# CD.net
KiCad netlist of a schematic drawn in EAGLE
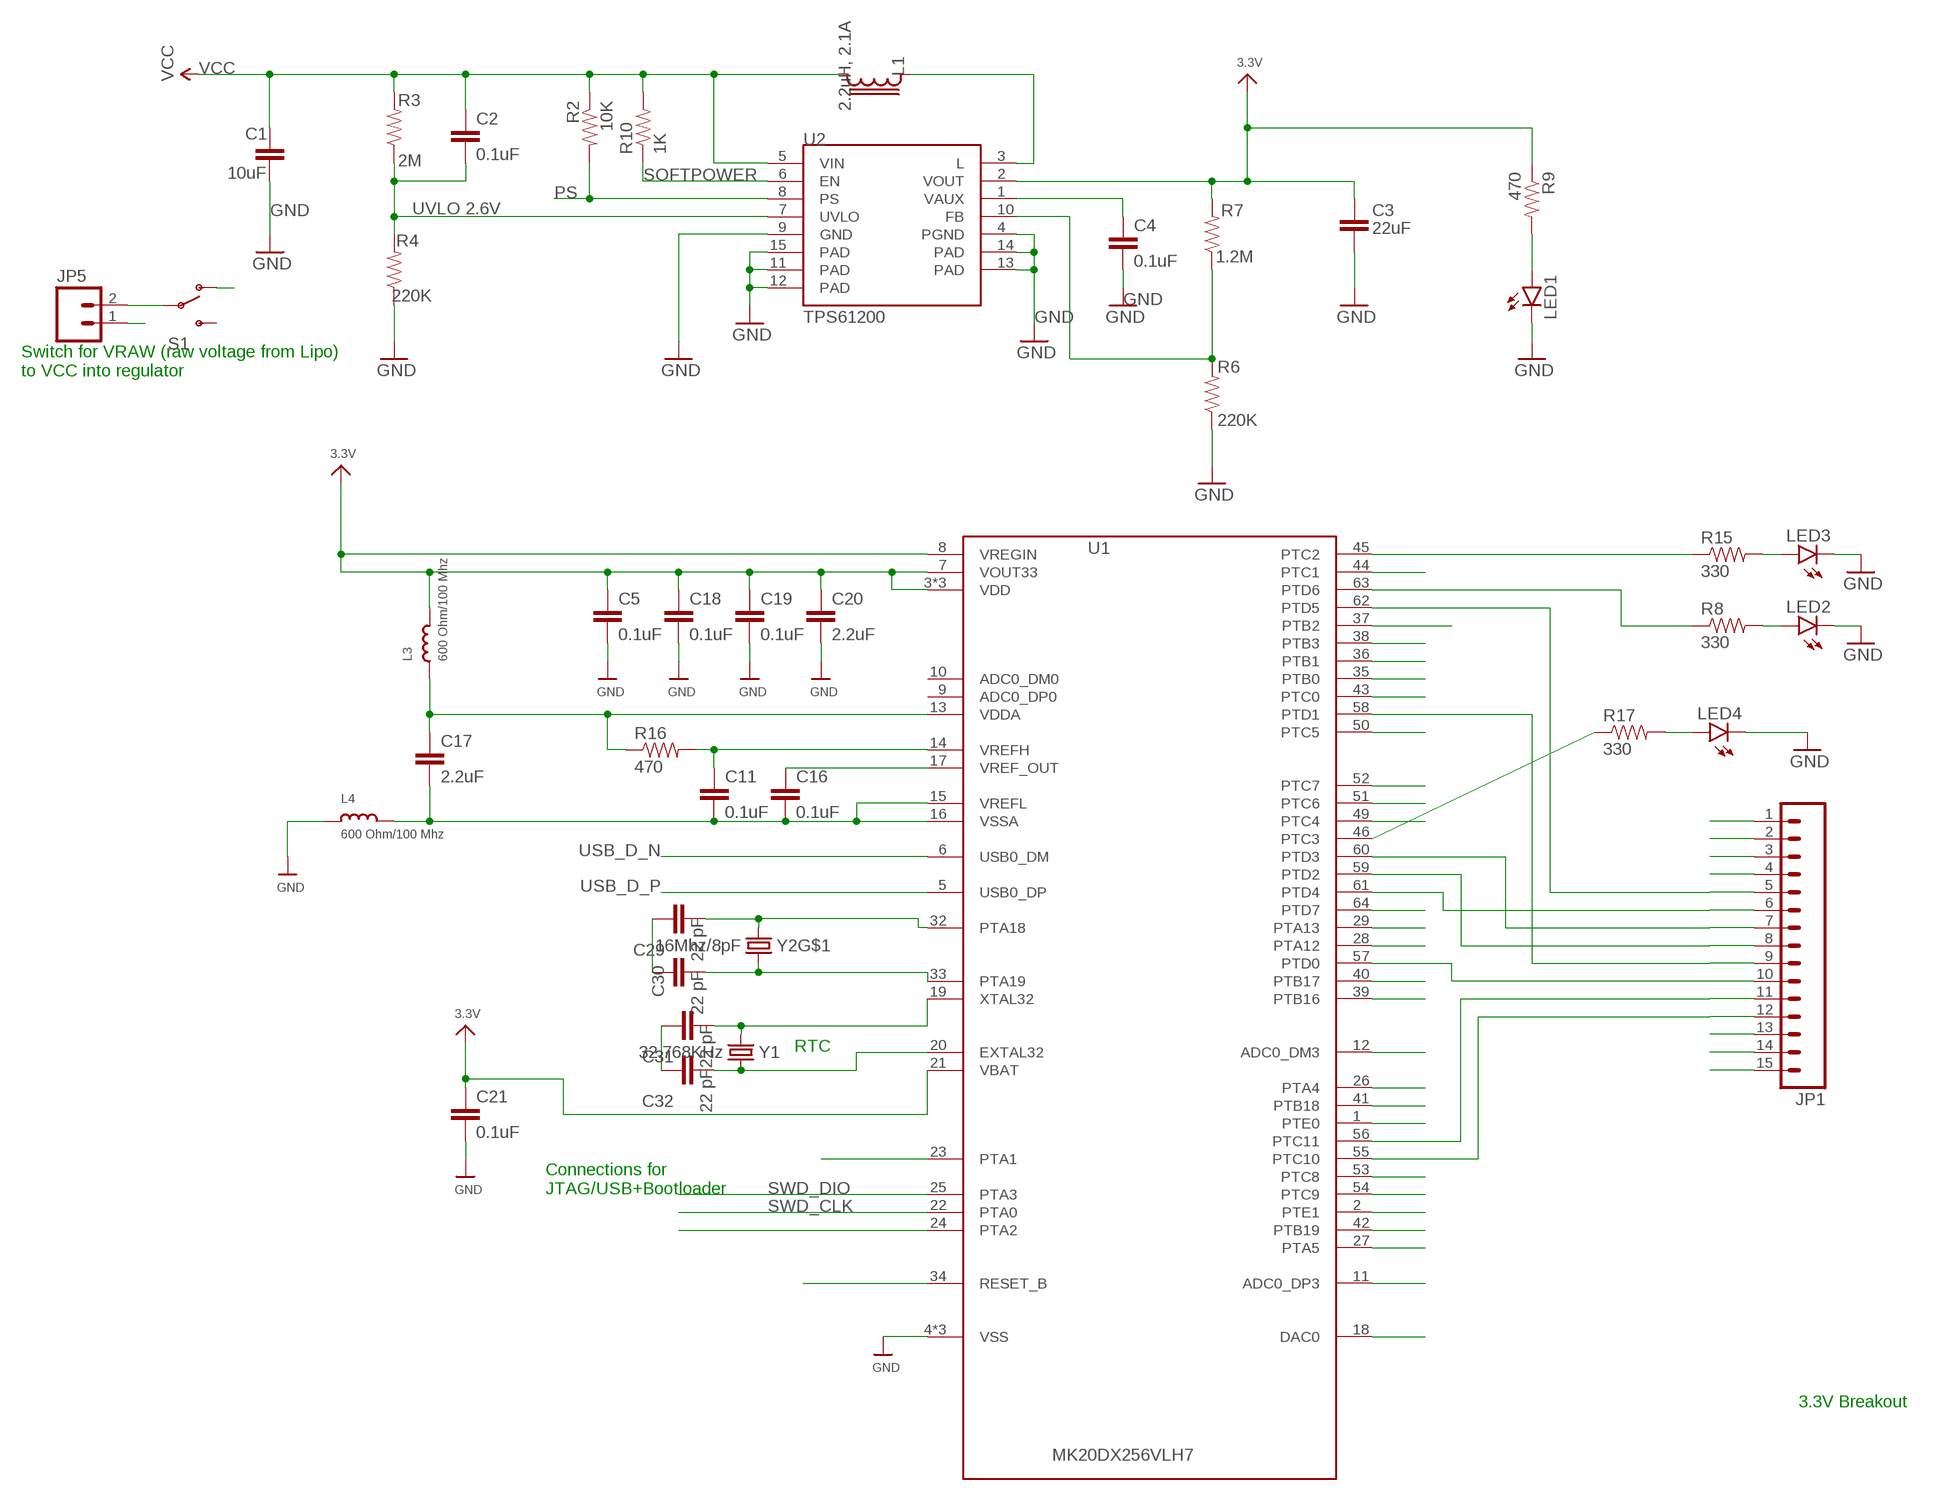
[diagram p0: schematic, sheet 1]
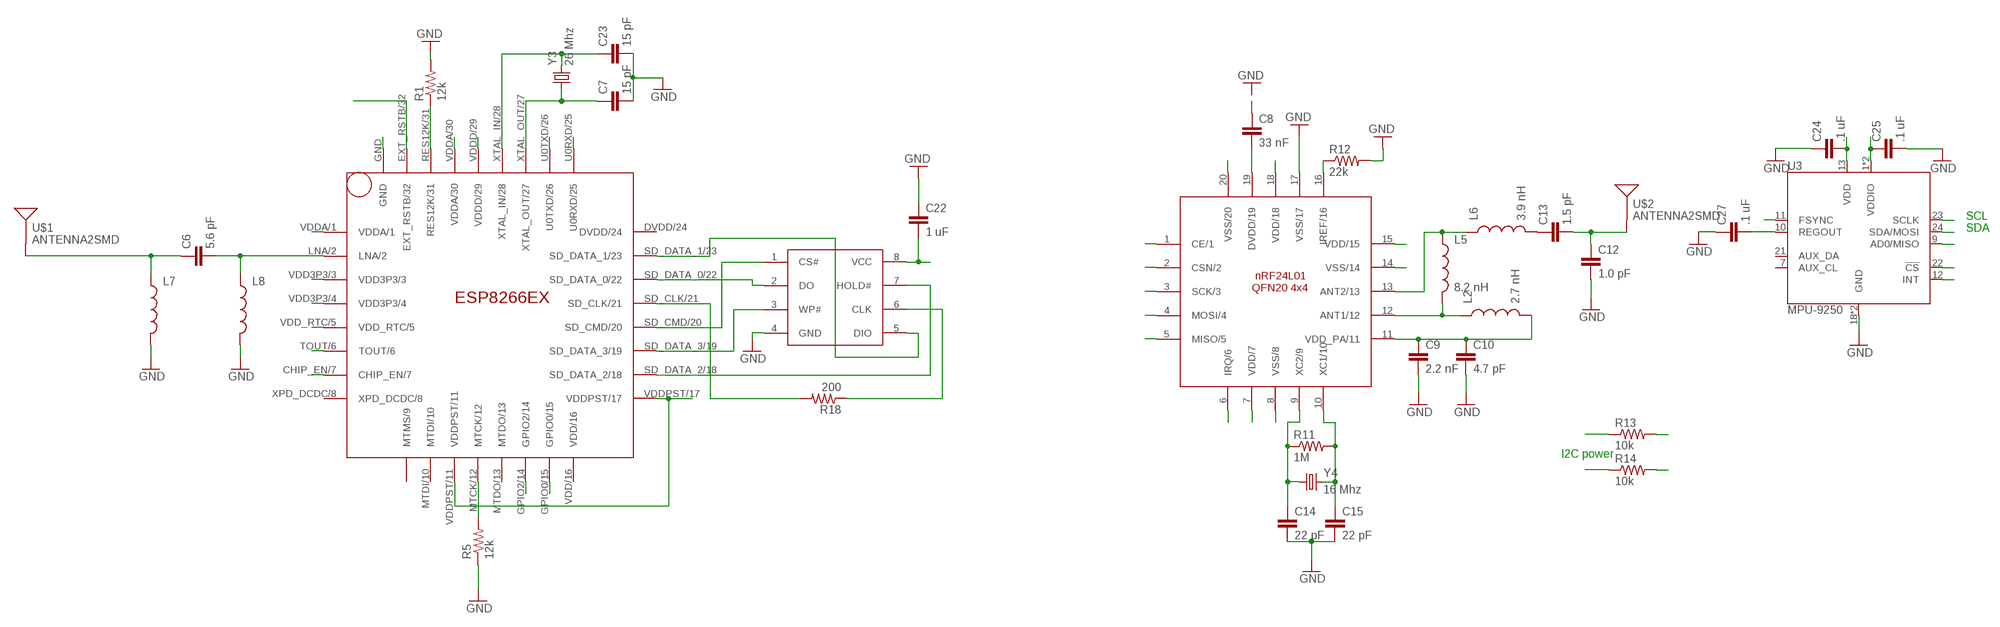
[diagram p1: schematic, sheet 2]

(export (version "E")
  (design (tool "Eeschema 10.0.6"))
  (components
    (comp (ref "C6")
      (value "5.6 pF")
      (footprint "eagle-import:0603-CAP")
      (libsource (lib "eagle-import") (part "CAP0603-CAP"))
    )
    (comp (ref "C7")
      (value "15 pF")
      (footprint "eagle-import:0603-CAP")
      (libsource (lib "eagle-import") (part "CAP0603-CAP"))
    )
    (comp (ref "C8")
      (value "33 nF")
      (footprint "eagle-import:0603-CAP")
      (libsource (lib "eagle-import") (part "CAP0603-CAP"))
    )
    (comp (ref "C9")
      (value "2.2 nF")
      (footprint "eagle-import:0603-CAP")
      (libsource (lib "eagle-import") (part "CAP0603-CAP"))
    )
    (comp (ref "C10")
      (value "4.7 pF")
      (footprint "eagle-import:0603-CAP")
      (libsource (lib "eagle-import") (part "CAP0603-CAP"))
    )
    (comp (ref "C12")
      (value "1.0 pF")
      (footprint "eagle-import:0603-CAP")
      (libsource (lib "eagle-import") (part "CAP0603-CAP"))
    )
    (comp (ref "C13")
      (value "1.5 pF")
      (footprint "eagle-import:0603-CAP")
      (libsource (lib "eagle-import") (part "CAP0603-CAP"))
    )
    (comp (ref "C14")
      (value "22 pF")
      (footprint "eagle-import:0603-CAP")
      (libsource (lib "eagle-import") (part "CAP0603-CAP"))
    )
    (comp (ref "C15")
      (value "22 pF")
      (footprint "eagle-import:0603-CAP")
      (libsource (lib "eagle-import") (part "CAP0603-CAP"))
    )
    (comp (ref "C22")
      (value "1 uF")
      (footprint "eagle-import:0603-CAP")
      (libsource (lib "eagle-import") (part "CAP0603-CAP"))
    )
    (comp (ref "C23")
      (value "15 pF")
      (footprint "eagle-import:0603-CAP")
      (libsource (lib "eagle-import") (part "CAP0603-CAP"))
    )
    (comp (ref "C24")
      (value ".1 uF")
      (footprint "eagle-import:0603-CAP")
      (libsource (lib "eagle-import") (part "CAP0603-CAP"))
    )
    (comp (ref "C25")
      (value ".1 uF")
      (footprint "eagle-import:0603-CAP")
      (libsource (lib "eagle-import") (part "CAP0603-CAP"))
    )
    (comp (ref "C27")
      (value ".1 uF")
      (footprint "eagle-import:0603-CAP")
      (libsource (lib "eagle-import") (part "CAP0603-CAP"))
    )
    (comp (ref "L2")
      (value "2.7 nH")
      (footprint "eagle-import:C0402")
      (libsource (lib "eagle-import") (part "INDUCTOR0402"))
    )
    (comp (ref "L5")
      (value "8.2 nH")
      (footprint "eagle-import:C0402")
      (libsource (lib "eagle-import") (part "INDUCTOR0402"))
    )
    (comp (ref "L6")
      (value "3.9 nH")
      (footprint "eagle-import:C0402")
      (libsource (lib "eagle-import") (part "INDUCTOR0402"))
    )
    (comp (ref "L7")
      (value "INDUCTOR30OHM,1.8A")
      (footprint "eagle-import:0603")
      (libsource (lib "eagle-import") (part "INDUCTOR30OHM,1.8A"))
    )
    (comp (ref "L8")
      (value "INDUCTOR30OHM,1.8A")
      (footprint "eagle-import:0603")
      (libsource (lib "eagle-import") (part "INDUCTOR30OHM,1.8A"))
    )
    (comp (ref "R1")
      (value "12k")
      (footprint "eagle-import:0603-RES")
      (libsource (lib "eagle-import") (part "RESISTOR0603-RES"))
    )
    (comp (ref "R5")
      (value "12k")
      (footprint "eagle-import:0603-RES")
      (libsource (lib "eagle-import") (part "RESISTOR0603-RES"))
    )
    (comp (ref "R11")
      (value "1M")
      (footprint "eagle-import:0603-RES")
      (libsource (lib "eagle-import") (part "RESISTOR0603-RES"))
    )
    (comp (ref "R12")
      (value "22k")
      (footprint "eagle-import:0603-RES")
      (libsource (lib "eagle-import") (part "RESISTOR0603-RES"))
    )
    (comp (ref "R13")
      (value "10k")
      (footprint "eagle-import:0603-RES")
      (libsource (lib "eagle-import") (part "RESISTOR0603-RES"))
    )
    (comp (ref "R14")
      (value "10k")
      (footprint "eagle-import:0603-RES")
      (libsource (lib "eagle-import") (part "RESISTOR0603-RES"))
    )
    (comp (ref "R18")
      (value "200")
      (footprint "eagle-import:0603-RES")
      (libsource (lib "eagle-import") (part "RESISTOR0603-RES"))
    )
    (comp (ref "U$1")
      (value "ANTENNA2SMD")
      (footprint "eagle-import:ANTENNA-CHIP2")
      (libsource (lib "eagle-import") (part "ANTENNA2SMD"))
    )
    (comp (ref "U$2")
      (value "ANTENNA2SMD")
      (footprint "eagle-import:ANTENNA-CHIP2")
      (libsource (lib "eagle-import") (part "ANTENNA2SMD"))
    )
    (comp (ref "U$3")
      (value "25Q40")
      (footprint "eagle-import:SOP8")
      (libsource (lib "eagle-import") (part "25Q40"))
    )
    (comp (ref "U$4")
      (value "NRF24L01")
      (footprint "eagle-import:QFN20(4X4)")
      (libsource (lib "eagle-import") (part "NRF24L01"))
    )
    (comp (ref "U$6")
      (value "ESP8266EX")
      (footprint "eagle-import:QFN32")
      (libsource (lib "eagle-import") (part "ESP8266EX"))
    )
    (comp (ref "U3")
      (value "MPU-9250")
      (footprint "eagle-import:QFN-24_3MM")
      (libsource (lib "eagle-import") (part "MPU-9250"))
    )
    (comp (ref "Y3")
      (value "26 Mhz")
      (footprint "eagle-import:CRYSTAL-SMD-5X3")
      (libsource (lib "eagle-import") (part "CRYSTAL5X3"))
    )
    (comp (ref "Y4")
      (value "16 Mhz")
      (footprint "eagle-import:CRYSTAL-SMD-5X3")
      (libsource (lib "eagle-import") (part "CRYSTAL5X3"))
    )
    (comp (ref "C1")
      (value "10uF")
      (footprint "eagle-import:0603-CAP")
      (fields (field (name "MF") "Murata") (field (name "MPN") "GRM188R60J106ME47D"))
      (libsource (lib "eagle-import") (part "CAPACITOR-10UF"))
    )
    (comp (ref "C2")
      (value "0.1uF")
      (footprint "eagle-import:0603-CAP")
      (fields (field (name "MF") "Kemet") (field (name "MPN") "C0603C104J3RACTU"))
      (libsource (lib "eagle-import") (part "CAPACITOR-0.1UF"))
    )
    (comp (ref "C3")
      (value "22uF")
      (footprint "eagle-import:0603-CAP")
      (fields (field (name "MF") "Murata") (field (name "MPN") "GRM188R60J226MEA0D"))
      (libsource (lib "eagle-import") (part "CAPACITOR-22UF"))
    )
    (comp (ref "C4")
      (value "0.1uF")
      (footprint "eagle-import:0603-CAP")
      (fields (field (name "MF") "Kemet") (field (name "MPN") "C0603C104J3RACTU"))
      (libsource (lib "eagle-import") (part "CAPACITOR-0.1UF"))
    )
    (comp (ref "C5")
      (value "0.1uF")
      (footprint "eagle-import:0603-CAP")
      (fields (field (name "MF") "Kemet") (field (name "MPN") "C0603C104J3RACTU"))
      (libsource (lib "eagle-import") (part "CAPACITOR-0.1UF"))
    )
    (comp (ref "C11")
      (value "0.1uF")
      (footprint "eagle-import:0603-CAP")
      (fields (field (name "MF") "Kemet") (field (name "MPN") "C0603C104J3RACTU"))
      (libsource (lib "eagle-import") (part "CAPACITOR-0.1UF"))
    )
    (comp (ref "C16")
      (value "0.1uF")
      (footprint "eagle-import:0603-CAP")
      (fields (field (name "MF") "Kemet") (field (name "MPN") "C0603C104J3RACTU"))
      (libsource (lib "eagle-import") (part "CAPACITOR-0.1UF"))
    )
    (comp (ref "C17")
      (value "2.2uF")
      (footprint "eagle-import:0603-CAP")
      (fields (field (name "MF") "Kemet") (field (name "MPN") "C0603C225K4PACTU"))
      (libsource (lib "eagle-import") (part "CAPACITOR-2.2UF"))
    )
    (comp (ref "C18")
      (value "0.1uF")
      (footprint "eagle-import:0603-CAP")
      (fields (field (name "MF") "Kemet") (field (name "MPN") "C0603C104J3RACTU"))
      (libsource (lib "eagle-import") (part "CAPACITOR-0.1UF"))
    )
    (comp (ref "C19")
      (value "0.1uF")
      (footprint "eagle-import:0603-CAP")
      (fields (field (name "MF") "Kemet") (field (name "MPN") "C0603C104J3RACTU"))
      (libsource (lib "eagle-import") (part "CAPACITOR-0.1UF"))
    )
    (comp (ref "C20")
      (value "2.2uF")
      (footprint "eagle-import:0603-CAP")
      (fields (field (name "MF") "Kemet") (field (name "MPN") "C0603C225K4PACTU"))
      (libsource (lib "eagle-import") (part "CAPACITOR-2.2UF"))
    )
    (comp (ref "C21")
      (value "0.1uF")
      (footprint "eagle-import:0603-CAP")
      (fields (field (name "MF") "Kemet") (field (name "MPN") "C0603C104J3RACTU"))
      (libsource (lib "eagle-import") (part "CAPACITOR-0.1UF"))
    )
    (comp (ref "C29")
      (value "22 pF")
      (footprint "eagle-import:0603-CAP")
      (fields (field (name "MF") "Murata") (field (name "MPN") "GRM188R60J106ME47D"))
      (libsource (lib "eagle-import") (part "CAPACITOR-10UF"))
    )
    (comp (ref "C30")
      (value "22 pF")
      (footprint "eagle-import:0603-CAP")
      (fields (field (name "MF") "Murata") (field (name "MPN") "GRM188R60J106ME47D"))
      (libsource (lib "eagle-import") (part "CAPACITOR-10UF"))
    )
    (comp (ref "C31")
      (value "22 pF")
      (footprint "eagle-import:0603-CAP")
      (fields (field (name "MF") "Murata") (field (name "MPN") "GRM188R60J106ME47D"))
      (libsource (lib "eagle-import") (part "CAPACITOR-10UF"))
    )
    (comp (ref "C32")
      (value "22 pF")
      (footprint "eagle-import:0603-CAP")
      (fields (field (name "MF") "Murata") (field (name "MPN") "GRM188R60J106ME47D"))
      (libsource (lib "eagle-import") (part "CAPACITOR-10UF"))
    )
    (comp (ref "JP1")
      (value "M15")
      (footprint "eagle-import:1X15")
      (libsource (lib "eagle-import") (part "M15"))
    )
    (comp (ref "JP5")
      (value "M02PTH")
      (footprint "eagle-import:1X02")
      (libsource (lib "eagle-import") (part "M02PTH"))
    )
    (comp (ref "L1")
      (value "2.2uH, 2.1A")
      (footprint "eagle-import:LPS3015")
      (fields (field (name "MF") "Coilcraft") (field (name "MPN") "LPS3015-222MRB"))
      (libsource (lib "eagle-import") (part "LPS30152.2UH"))
    )
    (comp (ref "L3")
      (value "600 Ohm/100 Mhz")
      (footprint "eagle-import:0805")
      (fields (field (name "MF") "Taiyo Yuden") (field (name "MPN") "BK2125HM601-T"))
      (libsource (lib "eagle-import") (part "INDUCTOR-BK2125HM601-T"))
    )
    (comp (ref "L4")
      (value "600 Ohm/100 Mhz")
      (footprint "eagle-import:0805")
      (fields (field (name "MF") "Taiyo Yuden") (field (name "MPN") "BK2125HM601-T"))
      (libsource (lib "eagle-import") (part "INDUCTOR-BK2125HM601-T"))
    )
    (comp (ref "LED1")
      (value "LED-GREEN")
      (footprint "eagle-import:LED-0603")
      (fields (field (name "MF") "Avago") (field (name "MPN") "HSMG-C190"))
      (libsource (lib "eagle-import") (part "LED-GREEN"))
    )
    (comp (ref "LED2")
      (value "LED-GREEN")
      (footprint "eagle-import:LED-0603")
      (fields (field (name "MF") "Avago") (field (name "MPN") "HSMG-C190"))
      (libsource (lib "eagle-import") (part "LED-GREEN"))
    )
    (comp (ref "LED3")
      (value "LED-GREEN")
      (footprint "eagle-import:LED-0603")
      (fields (field (name "MF") "Avago") (field (name "MPN") "HSMG-C190"))
      (libsource (lib "eagle-import") (part "LED-GREEN"))
    )
    (comp (ref "LED4")
      (value "LED-GREEN")
      (footprint "eagle-import:LED-0603")
      (fields (field (name "MF") "Avago") (field (name "MPN") "HSMG-C190"))
      (libsource (lib "eagle-import") (part "LED-GREEN"))
    )
    (comp (ref "R2")
      (value "10K")
      (footprint "eagle-import:0603-RES")
      (fields (field (name "MF") "Panasonic") (field (name "MPN") "ERJ-3GEYJ103V"))
      (libsource (lib "eagle-import") (part "RESISTOR-10K"))
    )
    (comp (ref "R3")
      (value "2M")
      (footprint "eagle-import:0603-RES")
      (fields (field (name "MF") "Panasonic") (field (name "MPN") "ERJ-3GEYJ205V"))
      (libsource (lib "eagle-import") (part "RESISTOR-2M"))
    )
    (comp (ref "R4")
      (value "220K")
      (footprint "eagle-import:0603-RES")
      (fields (field (name "MF") "Panasonic") (field (name "MPN") "ERJ-3GEYJ224V"))
      (libsource (lib "eagle-import") (part "RESISTOR-220K"))
    )
    (comp (ref "R6")
      (value "220K")
      (footprint "eagle-import:0603-RES")
      (fields (field (name "MF") "Panasonic") (field (name "MPN") "ERJ-3GEYJ224V"))
      (libsource (lib "eagle-import") (part "RESISTOR-220K"))
    )
    (comp (ref "R7")
      (value "1.2M")
      (footprint "eagle-import:0603-RES")
      (fields (field (name "MF") "Panasonic") (field (name "MPN") "ERJ-3GEYJ125V"))
      (libsource (lib "eagle-import") (part "RESISTOR-1.2M"))
    )
    (comp (ref "R8")
      (value "330")
      (footprint "eagle-import:0603-RES")
      (fields (field (name "MF") "Panasonic") (field (name "MPN") "ERJ-3GEYJ471V"))
      (libsource (lib "eagle-import") (part "RESISTOR-470"))
    )
    (comp (ref "R9")
      (value "470")
      (footprint "eagle-import:0603-RES")
      (fields (field (name "MF") "Panasonic") (field (name "MPN") "ERJ-3GEYJ471V"))
      (libsource (lib "eagle-import") (part "RESISTOR-470"))
    )
    (comp (ref "R10")
      (value "1K")
      (footprint "eagle-import:0603-RES")
      (fields (field (name "MF") "Panasonic") (field (name "MPN") "ERJ-3GEYJ102V"))
      (libsource (lib "eagle-import") (part "RESISTOR-1K"))
    )
    (comp (ref "R15")
      (value "330")
      (footprint "eagle-import:0603-RES")
      (fields (field (name "MF") "Panasonic") (field (name "MPN") "ERJ-3GEYJ471V"))
      (libsource (lib "eagle-import") (part "RESISTOR-470"))
    )
    (comp (ref "R16")
      (value "470")
      (footprint "eagle-import:0603-RES")
      (fields (field (name "MF") "Panasonic") (field (name "MPN") "ERJ-3GEYJ471V"))
      (libsource (lib "eagle-import") (part "RESISTOR-470"))
    )
    (comp (ref "R17")
      (value "330")
      (footprint "eagle-import:0603-RES")
      (fields (field (name "MF") "Panasonic") (field (name "MPN") "ERJ-3GEYJ471V"))
      (libsource (lib "eagle-import") (part "RESISTOR-470"))
    )
    (comp (ref "S1")
      (value "SWITCH-SPDT-SMD-A")
      (footprint "eagle-import:SWITCH-SPST-SMD-A")
      (libsource (lib "eagle-import") (part "SWITCH-SPDT-SMD-A"))
    )
    (comp (ref "U1")
      (value "MK20DX256VLH7")
      (footprint "eagle-import:MK20DX256VLH7")
      (fields (field (name "MF") "Freescale"))
      (libsource (lib "eagle-import") (part "MK20DX256VLH7"))
    )
    (comp (ref "U2")
      (value "TPS61200")
      (footprint "eagle-import:QFN-10_PAD")
      (fields (field (name "MF") "Texas Instruments") (field (name "MPN") "TPS61200DRCR"))
      (libsource (lib "eagle-import") (part "TPS61200"))
    )
    (comp (ref "Y1")
      (value "32.768KHz")
      (footprint "eagle-import:CRYSTAL-TXC-7A")
      (fields (field (name "MF") "Epson Timing") (field (name "MPN") "FC-255 32.7680K-A3"))
      (libsource (lib "eagle-import") (part "CRYSTAL/32.768KHZ/SMD-TXC_7A"))
    )
    (comp (ref "Y2")
      (value "16Mhz/8pF")
      (footprint "eagle-import:CRYSTAL-SMD-5X3")
      (fields (field (name "MF") "ECS") (field (name "MPN") "ECS-160-8-30B-CKM"))
      (libsource (lib "eagle-import") (part "CRYSTAL/SMD-5X3-GND16MHZ/8PF"))
    )
  )
  (nets
    (net (code "1") (name "3.3V") (class "Default")
      (node (ref "C18") (pin "1") (pinfunction "1_1") (pintype "passive"))
      (node (ref "C19") (pin "1") (pinfunction "1_1") (pintype "passive"))
      (node (ref "C20") (pin "1") (pinfunction "1_1") (pintype "passive"))
      (node (ref "C21") (pin "1") (pinfunction "1_1") (pintype "passive"))
      (node (ref "C22") (pin "2") (pinfunction "2_2") (pintype "passive"))
      (node (ref "C24") (pin "2") (pinfunction "2_2") (pintype "passive"))
      (node (ref "C25") (pin "1") (pinfunction "1_1") (pintype "passive"))
      (node (ref "C3") (pin "1") (pinfunction "1_1") (pintype "passive"))
      (node (ref "C5") (pin "1") (pinfunction "1_1") (pintype "passive"))
      (node (ref "JP1") (pin "13") (pinfunction "13_13") (pintype "passive"))
      (node (ref "JP1") (pin "14") (pinfunction "14_14") (pintype "passive"))
      (node (ref "JP1") (pin "15") (pinfunction "15_15") (pintype "passive"))
      (node (ref "L3") (pin "2") (pinfunction "2_2") (pintype "passive"))
      (node (ref "R13") (pin "1") (pinfunction "1_1") (pintype "passive"))
      (node (ref "R14") (pin "1") (pinfunction "1_1") (pintype "passive"))
      (node (ref "R7") (pin "2") (pinfunction "2_2") (pintype "passive"))
      (node (ref "R9") (pin "1") (pinfunction "1_1") (pintype "passive"))
      (node (ref "U$3") (pin "8") (pinfunction "VCC_8") (pintype "bidirectional"))
      (node (ref "U$4") (pin "15") (pinfunction "VDD/15_15") (pintype "bidirectional"))
      (node (ref "U$4") (pin "18") (pinfunction "VDD/18_18") (pintype "bidirectional"))
      (node (ref "U$4") (pin "7") (pinfunction "VDD/7_7") (pintype "bidirectional"))
      (node (ref "U$6") (pin "VDD3P3/3") (pinfunction "VDD3P3/3_VDD3P3/3") (pintype "bidirectional"))
      (node (ref "U$6") (pin "VDD3P3/4") (pinfunction "VDD3P3/4_VDD3P3/4") (pintype "bidirectional"))
      (node (ref "U$6") (pin "VDDA/1") (pinfunction "VDDA/1_VDDA/1") (pintype "bidirectional"))
      (node (ref "U$6") (pin "VDDD/29") (pinfunction "VDDD/29_VDDD/29") (pintype "bidirectional"))
      (node (ref "U$6") (pin "VDDPST/11") (pinfunction "VDDPST/11_VDDPST/11") (pintype "bidirectional"))
      (node (ref "U$6") (pin "VDDPST/17") (pinfunction "VDDPST/17_VDDPST/17") (pintype "bidirectional"))
      (node (ref "U1") (pin "21") (pinfunction "VBAT_21") (pintype "bidirectional"))
      (node (ref "U1") (pin "3") (pinfunction "VDD_3") (pintype "bidirectional"))
      (node (ref "U1") (pin "30") (pinfunction "VDD_30") (pintype "bidirectional"))
      (node (ref "U1") (pin "48") (pinfunction "VDD_48") (pintype "bidirectional"))
      (node (ref "U1") (pin "7") (pinfunction "VOUT33_7") (pintype "bidirectional"))
      (node (ref "U1") (pin "8") (pinfunction "VREGIN_8") (pintype "bidirectional"))
      (node (ref "U2") (pin "2") (pinfunction "VOUT_2") (pintype "passive"))
      (node (ref "U3") (pin "1") (pinfunction "VDDIO_1") (pintype "bidirectional"))
      (node (ref "U3") (pin "13") (pinfunction "VDD_13") (pintype "bidirectional"))
      (node (ref "U3") (pin "22") (pinfunction "~{CS}_22") (pintype "bidirectional"))
      (node (ref "U3") (pin "8") (pinfunction "VDDIO_8") (pintype "bidirectional"))
    )
    (net (code "2") (name "AD0") (class "Default")
      (node (ref "U1") (pin "39") (pinfunction "PTB16_39") (pintype "bidirectional"))
      (node (ref "U3") (pin "9") (pinfunction "AD0/MISO_9") (pintype "bidirectional"))
    )
    (net (code "3") (name "GND") (class "Default")
      (node (ref "C1") (pin "2") (pinfunction "2_2") (pintype "passive"))
      (node (ref "C10") (pin "2") (pinfunction "2_2") (pintype "passive"))
      (node (ref "C12") (pin "2") (pinfunction "2_2") (pintype "passive"))
      (node (ref "C14") (pin "2") (pinfunction "2_2") (pintype "passive"))
      (node (ref "C15") (pin "2") (pinfunction "2_2") (pintype "passive"))
      (node (ref "C18") (pin "2") (pinfunction "2_2") (pintype "passive"))
      (node (ref "C19") (pin "2") (pinfunction "2_2") (pintype "passive"))
      (node (ref "C20") (pin "2") (pinfunction "2_2") (pintype "passive"))
      (node (ref "C21") (pin "2") (pinfunction "2_2") (pintype "passive"))
      (node (ref "C22") (pin "1") (pinfunction "1_1") (pintype "passive"))
      (node (ref "C23") (pin "2") (pinfunction "2_2") (pintype "passive"))
      (node (ref "C24") (pin "1") (pinfunction "1_1") (pintype "passive"))
      (node (ref "C25") (pin "2") (pinfunction "2_2") (pintype "passive"))
      (node (ref "C27") (pin "1") (pinfunction "1_1") (pintype "passive"))
      (node (ref "C29") (pin "1") (pinfunction "1_1") (pintype "passive"))
      (node (ref "C3") (pin "2") (pinfunction "2_2") (pintype "passive"))
      (node (ref "C30") (pin "1") (pinfunction "1_1") (pintype "passive"))
      (node (ref "C31") (pin "1") (pinfunction "1_1") (pintype "passive"))
      (node (ref "C32") (pin "1") (pinfunction "1_1") (pintype "passive"))
      (node (ref "C4") (pin "2") (pinfunction "2_2") (pintype "passive"))
      (node (ref "C5") (pin "2") (pinfunction "2_2") (pintype "passive"))
      (node (ref "C7") (pin "2") (pinfunction "2_2") (pintype "passive"))
      (node (ref "C8") (pin "1") (pinfunction "1_1") (pintype "passive"))
      (node (ref "C9") (pin "2") (pinfunction "2_2") (pintype "passive"))
      (node (ref "JP1") (pin "1") (pinfunction "1_1") (pintype "passive"))
      (node (ref "JP1") (pin "2") (pinfunction "2_2") (pintype "passive"))
      (node (ref "JP1") (pin "3") (pinfunction "3_3") (pintype "passive"))
      (node (ref "JP1") (pin "4") (pinfunction "4_4") (pintype "passive"))
      (node (ref "JP5") (pin "1") (pinfunction "1_1") (pintype "passive"))
      (node (ref "L4") (pin "1") (pinfunction "1_1") (pintype "passive"))
      (node (ref "L7") (pin "2") (pinfunction "2_2") (pintype "passive"))
      (node (ref "L8") (pin "2") (pinfunction "2_2") (pintype "passive"))
      (node (ref "LED1") (pin "C") (pinfunction "C_C") (pintype "passive"))
      (node (ref "LED2") (pin "C") (pinfunction "C_C") (pintype "passive"))
      (node (ref "LED3") (pin "C") (pinfunction "C_C") (pintype "passive"))
      (node (ref "LED4") (pin "C") (pinfunction "C_C") (pintype "passive"))
      (node (ref "R1") (pin "2") (pinfunction "2_2") (pintype "passive"))
      (node (ref "R12") (pin "2") (pinfunction "2_2") (pintype "passive"))
      (node (ref "R4") (pin "1") (pinfunction "1_1") (pintype "passive"))
      (node (ref "R5") (pin "1") (pinfunction "1_1") (pintype "passive"))
      (node (ref "R6") (pin "1") (pinfunction "1_1") (pintype "passive"))
      (node (ref "U$3") (pin "4") (pinfunction "GND_4") (pintype "bidirectional"))
      (node (ref "U$4") (pin "14") (pinfunction "VSS/14_14") (pintype "bidirectional"))
      (node (ref "U$4") (pin "17") (pinfunction "VSS/17_17") (pintype "bidirectional"))
      (node (ref "U$4") (pin "20") (pinfunction "VSS/20_20") (pintype "bidirectional"))
      (node (ref "U$4") (pin "8") (pinfunction "VSS/8_8") (pintype "bidirectional"))
      (node (ref "U$6") (pin "GND") (pinfunction "GND_GND") (pintype "bidirectional"))
      (node (ref "U1") (pin "31") (pinfunction "VSS_31") (pintype "bidirectional"))
      (node (ref "U1") (pin "4") (pinfunction "VSS_4") (pintype "bidirectional"))
      (node (ref "U1") (pin "47") (pinfunction "VSS_47") (pintype "bidirectional"))
      (node (ref "U2") (pin "11") (pinfunction "PAD_11") (pintype "power_in"))
      (node (ref "U2") (pin "12") (pinfunction "PAD_12") (pintype "power_in"))
      (node (ref "U2") (pin "13") (pinfunction "PAD_13") (pintype "power_in"))
      (node (ref "U2") (pin "14") (pinfunction "PAD_14") (pintype "power_in"))
      (node (ref "U2") (pin "15") (pinfunction "PAD_15") (pintype "power_in"))
      (node (ref "U2") (pin "4") (pinfunction "PGND_4") (pintype "power_in"))
      (node (ref "U2") (pin "9") (pinfunction "GND_9") (pintype "power_in"))
      (node (ref "U3") (pin "18") (pinfunction "GND_18") (pintype "bidirectional"))
      (node (ref "U3") (pin "20") (pinfunction "GND_20") (pintype "bidirectional"))
    )
    (net (code "4") (name "Net-(C6-Pad2)") (class "Default")
      (node (ref "C6") (pin "2") (pinfunction "2_2") (pintype "passive"))
      (node (ref "L8") (pin "1") (pinfunction "1_1") (pintype "passive"))
      (node (ref "U$6") (pin "LNA/2") (pinfunction "LNA/2_LNA/2") (pintype "bidirectional"))
    )
    (net (code "5") (name "Net-(C7-Pad1)") (class "Default")
      (node (ref "C7") (pin "1") (pinfunction "1_1") (pintype "passive"))
      (node (ref "U$6") (pin "XTAL_OUT/27") (pinfunction "XTAL_OUT/27_XTAL_OUT/27") (pintype "bidirectional"))
      (node (ref "Y3") (pin "1") (pinfunction "1_1") (pintype "passive"))
    )
    (net (code "6") (name "Net-(C13-Pad1)") (class "Default")
      (node (ref "C13") (pin "1") (pinfunction "1_1") (pintype "passive"))
      (node (ref "L6") (pin "2") (pinfunction "2_2") (pintype "passive"))
    )
    (net (code "7") (name "Net-(LED1-PadA)") (class "Default")
      (node (ref "LED1") (pin "A") (pinfunction "A_A") (pintype "passive"))
      (node (ref "R9") (pin "2") (pinfunction "2_2") (pintype "passive"))
    )
    (net (code "8") (name "Net-(LED2-PadA)") (class "Default")
      (node (ref "LED2") (pin "A") (pinfunction "A_A") (pintype "passive"))
      (node (ref "R8") (pin "2") (pinfunction "2_2") (pintype "passive"))
    )
    (net (code "9") (name "Net-(LED3-PadA)") (class "Default")
      (node (ref "LED3") (pin "A") (pinfunction "A_A") (pintype "passive"))
      (node (ref "R15") (pin "2") (pinfunction "2_2") (pintype "passive"))
    )
    (net (code "10") (name "Net-(LED4-PadA)") (class "Default")
      (node (ref "LED4") (pin "A") (pinfunction "A_A") (pintype "passive"))
      (node (ref "R17") (pin "2") (pinfunction "2_2") (pintype "passive"))
    )
    (net (code "11") (name "Net-(R1-Pad1)") (class "Default")
      (node (ref "R1") (pin "1") (pinfunction "1_1") (pintype "passive"))
      (node (ref "U$6") (pin "RES12K/31") (pinfunction "RES12K/31_RES12K/31") (pintype "bidirectional"))
    )
    (net (code "12") (name "Net-(R5-Pad2)") (class "Default")
      (node (ref "R5") (pin "2") (pinfunction "2_2") (pintype "passive"))
      (node (ref "U$6") (pin "MTCK/12") (pinfunction "MTCK/12_MTCK/12") (pintype "bidirectional"))
    )
    (net (code "13") (name "Net-(R18-Pad2)") (class "Default")
      (node (ref "R18") (pin "2") (pinfunction "2_2") (pintype "passive"))
      (node (ref "U$6") (pin "SD_CLK/21") (pinfunction "SD_CLK/21_SD_CLK/21") (pintype "bidirectional"))
    )
    (net (code "14") (name "Net-(S1-P)") (class "Default")
      (node (ref "JP5") (pin "2") (pinfunction "2_2") (pintype "passive"))
      (node (ref "S1") (pin "2") (pinfunction "P_2") (pintype "passive"))
    )
    (net (code "15") (name "Net-(U$1-SIGNAL)") (class "Default")
      (node (ref "C6") (pin "1") (pinfunction "1_1") (pintype "passive"))
      (node (ref "L7") (pin "1") (pinfunction "1_1") (pintype "passive"))
      (node (ref "U$1") (pin "FEED") (pinfunction "SIGNAL_FEED") (pintype "bidirectional"))
    )
    (net (code "16") (name "Net-(U$2-SIGNAL)") (class "Default")
      (node (ref "C12") (pin "1") (pinfunction "1_1") (pintype "passive"))
      (node (ref "C13") (pin "2") (pinfunction "2_2") (pintype "passive"))
      (node (ref "U$2") (pin "FEED") (pinfunction "SIGNAL_FEED") (pintype "bidirectional"))
    )
    (net (code "17") (name "Net-(U$3-CLK)") (class "Default")
      (node (ref "R18") (pin "1") (pinfunction "1_1") (pintype "passive"))
      (node (ref "U$3") (pin "6") (pinfunction "CLK_6") (pintype "bidirectional"))
    )
    (net (code "18") (name "Net-(U$3-CS#)") (class "Default")
      (node (ref "U$3") (pin "1") (pinfunction "CS#_1") (pintype "bidirectional"))
      (node (ref "U$6") (pin "SD_CMD/20") (pinfunction "SD_CMD/20_SD_CMD/20") (pintype "bidirectional"))
    )
    (net (code "19") (name "Net-(U$3-DIO)") (class "Default")
      (node (ref "U$3") (pin "5") (pinfunction "DIO_5") (pintype "bidirectional"))
      (node (ref "U$6") (pin "SD_DATA_1/23") (pinfunction "SD_DATA_1/23_SD_DATA_1/23") (pintype "bidirectional"))
    )
    (net (code "20") (name "Net-(U$3-DO)") (class "Default")
      (node (ref "U$3") (pin "2") (pinfunction "DO_2") (pintype "bidirectional"))
      (node (ref "U$6") (pin "SD_DATA_0/22") (pinfunction "SD_DATA_0/22_SD_DATA_0/22") (pintype "bidirectional"))
    )
    (net (code "21") (name "Net-(U$3-HOLD#)") (class "Default")
      (node (ref "U$3") (pin "7") (pinfunction "HOLD#_7") (pintype "bidirectional"))
      (node (ref "U$6") (pin "SD_DATA_2/18") (pinfunction "SD_DATA_2/18_SD_DATA_2/18") (pintype "bidirectional"))
    )
    (net (code "22") (name "Net-(U$3-WP#)") (class "Default")
      (node (ref "U$3") (pin "3") (pinfunction "WP#_3") (pintype "bidirectional"))
      (node (ref "U$6") (pin "SD_DATA_3/19") (pinfunction "SD_DATA_3/19_SD_DATA_3/19") (pintype "bidirectional"))
    )
    (net (code "23") (name "Net-(U$4-ANT1{slash}12)") (class "Default")
      (node (ref "L2") (pin "1") (pinfunction "1_1") (pintype "passive"))
      (node (ref "L5") (pin "2") (pinfunction "2_2") (pintype "passive"))
      (node (ref "U$4") (pin "12") (pinfunction "ANT1/12_12") (pintype "bidirectional"))
    )
    (net (code "24") (name "Net-(U$4-ANT2{slash}13)") (class "Default")
      (node (ref "L5") (pin "1") (pinfunction "1_1") (pintype "passive"))
      (node (ref "L6") (pin "1") (pinfunction "1_1") (pintype "passive"))
      (node (ref "U$4") (pin "13") (pinfunction "ANT2/13_13") (pintype "bidirectional"))
    )
    (net (code "25") (name "Net-(U$4-DVDD{slash}19)") (class "Default")
      (node (ref "C8") (pin "2") (pinfunction "2_2") (pintype "passive"))
      (node (ref "U$4") (pin "19") (pinfunction "DVDD/19_19") (pintype "bidirectional"))
    )
    (net (code "26") (name "Net-(U$4-IREF{slash}16)") (class "Default")
      (node (ref "R12") (pin "1") (pinfunction "1_1") (pintype "passive"))
      (node (ref "U$4") (pin "16") (pinfunction "IREF/16_16") (pintype "bidirectional"))
    )
    (net (code "27") (name "Net-(U$4-VDD_PA{slash}11)") (class "Default")
      (node (ref "C10") (pin "1") (pinfunction "1_1") (pintype "passive"))
      (node (ref "C9") (pin "1") (pinfunction "1_1") (pintype "passive"))
      (node (ref "L2") (pin "2") (pinfunction "2_2") (pintype "passive"))
      (node (ref "U$4") (pin "11") (pinfunction "VDD_PA/11_11") (pintype "bidirectional"))
    )
    (net (code "28") (name "Net-(U$4-XC1{slash}10)") (class "Default")
      (node (ref "C15") (pin "1") (pinfunction "1_1") (pintype "passive"))
      (node (ref "R11") (pin "2") (pinfunction "2_2") (pintype "passive"))
      (node (ref "U$4") (pin "10") (pinfunction "XC1/10_10") (pintype "bidirectional"))
      (node (ref "Y4") (pin "3") (pinfunction "2_3") (pintype "passive"))
    )
    (net (code "29") (name "Net-(U$4-XC2{slash}9)") (class "Default")
      (node (ref "C14") (pin "1") (pinfunction "1_1") (pintype "passive"))
      (node (ref "R11") (pin "1") (pinfunction "1_1") (pintype "passive"))
      (node (ref "U$4") (pin "9") (pinfunction "XC2/9_9") (pintype "bidirectional"))
      (node (ref "Y4") (pin "1") (pinfunction "1_1") (pintype "passive"))
    )
    (net (code "30") (name "Net-(U1-EXTAL32)") (class "Default")
      (node (ref "C32") (pin "2") (pinfunction "2_2") (pintype "passive"))
      (node (ref "U1") (pin "20") (pinfunction "EXTAL32_20") (pintype "bidirectional"))
      (node (ref "Y1") (pin "P$1") (pinfunction "1_P$1") (pintype "passive"))
    )
    (net (code "31") (name "Net-(U1-PTA18)") (class "Default")
      (node (ref "C29") (pin "2") (pinfunction "2_2") (pintype "passive"))
      (node (ref "U1") (pin "32") (pinfunction "PTA18_32") (pintype "bidirectional"))
      (node (ref "Y2") (pin "3") (pinfunction "2_3") (pintype "passive"))
    )
    (net (code "32") (name "Net-(U1-PTA19)") (class "Default")
      (node (ref "C30") (pin "2") (pinfunction "2_2") (pintype "passive"))
      (node (ref "U1") (pin "33") (pinfunction "PTA19_33") (pintype "bidirectional"))
      (node (ref "Y2") (pin "1") (pinfunction "1_1") (pintype "passive"))
    )
    (net (code "33") (name "Net-(U1-PTC2)") (class "Default")
      (node (ref "R15") (pin "1") (pinfunction "1_1") (pintype "passive"))
      (node (ref "U1") (pin "45") (pinfunction "PTC2_45") (pintype "bidirectional"))
    )
    (net (code "34") (name "Net-(U1-PTC3)") (class "Default")
      (node (ref "R17") (pin "1") (pinfunction "1_1") (pintype "passive"))
      (node (ref "U1") (pin "46") (pinfunction "PTC3_46") (pintype "bidirectional"))
    )
    (net (code "35") (name "Net-(U1-PTD6)") (class "Default")
      (node (ref "R8") (pin "1") (pinfunction "1_1") (pintype "passive"))
      (node (ref "U1") (pin "63") (pinfunction "PTD6_63") (pintype "bidirectional"))
    )
    (net (code "36") (name "Net-(U1-VDDA)") (class "Default")
      (node (ref "C17") (pin "1") (pinfunction "1_1") (pintype "passive"))
      (node (ref "L3") (pin "1") (pinfunction "1_1") (pintype "passive"))
      (node (ref "R16") (pin "1") (pinfunction "1_1") (pintype "passive"))
      (node (ref "U1") (pin "13") (pinfunction "VDDA_13") (pintype "bidirectional"))
    )
    (net (code "37") (name "Net-(U1-VREFH)") (class "Default")
      (node (ref "C11") (pin "1") (pinfunction "1_1") (pintype "passive"))
      (node (ref "R16") (pin "2") (pinfunction "2_2") (pintype "passive"))
      (node (ref "U1") (pin "14") (pinfunction "VREFH_14") (pintype "bidirectional"))
    )
    (net (code "38") (name "Net-(U1-VREFL)") (class "Default")
      (node (ref "C11") (pin "2") (pinfunction "2_2") (pintype "passive"))
      (node (ref "C16") (pin "2") (pinfunction "2_2") (pintype "passive"))
      (node (ref "C17") (pin "2") (pinfunction "2_2") (pintype "passive"))
      (node (ref "L4") (pin "2") (pinfunction "2_2") (pintype "passive"))
      (node (ref "U1") (pin "15") (pinfunction "VREFL_15") (pintype "bidirectional"))
      (node (ref "U1") (pin "16") (pinfunction "VSSA_16") (pintype "bidirectional"))
    )
    (net (code "39") (name "Net-(U1-VREF_OUT)") (class "Default")
      (node (ref "C16") (pin "1") (pinfunction "1_1") (pintype "passive"))
      (node (ref "U1") (pin "17") (pinfunction "VREF_OUT_17") (pintype "bidirectional"))
    )
    (net (code "40") (name "Net-(U1-XTAL32)") (class "Default")
      (node (ref "C31") (pin "2") (pinfunction "2_2") (pintype "passive"))
      (node (ref "U1") (pin "19") (pinfunction "XTAL32_19") (pintype "bidirectional"))
      (node (ref "Y1") (pin "P$2") (pinfunction "2_P$2") (pintype "passive"))
    )
    (net (code "41") (name "Net-(U2-FB)") (class "Default")
      (node (ref "R6") (pin "2") (pinfunction "2_2") (pintype "passive"))
      (node (ref "R7") (pin "1") (pinfunction "1_1") (pintype "passive"))
      (node (ref "U2") (pin "10") (pinfunction "FB_10") (pintype "passive"))
    )
    (net (code "42") (name "Net-(U2-L)") (class "Default")
      (node (ref "L1") (pin "1") (pinfunction "1_1") (pintype "passive"))
      (node (ref "U2") (pin "3") (pinfunction "L_3") (pintype "passive"))
    )
    (net (code "43") (name "Net-(U2-UVLO)") (class "Default")
      (node (ref "C2") (pin "2") (pinfunction "2_2") (pintype "passive"))
      (node (ref "R3") (pin "1") (pinfunction "1_1") (pintype "passive"))
      (node (ref "R4") (pin "2") (pinfunction "2_2") (pintype "passive"))
      (node (ref "U2") (pin "7") (pinfunction "UVLO_7") (pintype "passive"))
    )
    (net (code "44") (name "Net-(U2-VAUX)") (class "Default")
      (node (ref "C4") (pin "1") (pinfunction "1_1") (pintype "passive"))
      (node (ref "U2") (pin "1") (pinfunction "VAUX_1") (pintype "passive"))
    )
    (net (code "45") (name "Net-(U3-REGOUT)") (class "Default")
      (node (ref "C27") (pin "2") (pinfunction "2_2") (pintype "passive"))
      (node (ref "U3") (pin "10") (pinfunction "REGOUT_10") (pintype "bidirectional"))
    )
    (net (code "46") (name "Net-(Y3-2)") (class "Default")
      (node (ref "C23") (pin "1") (pinfunction "1_1") (pintype "passive"))
      (node (ref "U$6") (pin "XTAL_IN/28") (pinfunction "XTAL_IN/28_XTAL_IN/28") (pintype "bidirectional"))
      (node (ref "Y3") (pin "3") (pinfunction "2_3") (pintype "passive"))
    )
    (net (code "47") (name "PS") (class "Default")
      (node (ref "R2") (pin "2") (pinfunction "2_2") (pintype "passive"))
      (node (ref "U2") (pin "8") (pinfunction "PS_8") (pintype "input"))
    )
    (net (code "48") (name "PTB0") (class "Default")
      (node (ref "U1") (pin "35") (pinfunction "PTB0_35") (pintype "bidirectional"))
      (node (ref "U3") (pin "12") (pinfunction "INT_12") (pintype "bidirectional"))
    )
    (net (code "49") (name "PTB1") (class "Default")
      (node (ref "U1") (pin "36") (pinfunction "PTB1_36") (pintype "bidirectional"))
      (node (ref "U3") (pin "11") (pinfunction "FSYNC_11") (pintype "bidirectional"))
    )
    (net (code "50") (name "PTB17") (class "Default")
      (node (ref "U$6") (pin "U0TXD/26") (pinfunction "U0TXD/26_U0TXD/26") (pintype "bidirectional"))
      (node (ref "U1") (pin "40") (pinfunction "PTB17_40") (pintype "bidirectional"))
    )
    (net (code "51") (name "PTB18") (class "Default")
      (node (ref "U$6") (pin "GPIO0/15") (pinfunction "GPIO0/15_GPIO0/15") (pintype "bidirectional"))
      (node (ref "U1") (pin "41") (pinfunction "PTB18_41") (pintype "bidirectional"))
    )
    (net (code "52") (name "PTB19") (class "Default")
      (node (ref "U$6") (pin "GPIO2/14") (pinfunction "GPIO2/14_GPIO2/14") (pintype "bidirectional"))
      (node (ref "U1") (pin "42") (pinfunction "PTB19_42") (pintype "bidirectional"))
    )
    (net (code "53") (name "PTC0") (class "Default")
      (node (ref "U$6") (pin "EXT_RSTB/32") (pinfunction "EXT_RSTB/32_EXT_RSTB/32") (pintype "bidirectional"))
      (node (ref "U1") (pin "43") (pinfunction "PTC0_43") (pintype "bidirectional"))
    )
    (net (code "54") (name "PTC1") (class "Default")
      (node (ref "U$6") (pin "CHIP_EN/7") (pinfunction "CHIP_EN/7_CHIP_EN/7") (pintype "bidirectional"))
      (node (ref "U1") (pin "44") (pinfunction "PTC1_44") (pintype "bidirectional"))
    )
    (net (code "55") (name "PTC4") (class "Default")
      (node (ref "U$4") (pin "2") (pinfunction "CSN/2_2") (pintype "bidirectional"))
      (node (ref "U1") (pin "49") (pinfunction "PTC4_49") (pintype "bidirectional"))
    )
    (net (code "56") (name "PTC5") (class "Default")
      (node (ref "U$4") (pin "3") (pinfunction "SCK/3_3") (pintype "bidirectional"))
      (node (ref "U1") (pin "50") (pinfunction "PTC5_50") (pintype "bidirectional"))
    )
    (net (code "57") (name "PTC6") (class "Default")
      (node (ref "U$4") (pin "4") (pinfunction "MOSI/4_4") (pintype "bidirectional"))
      (node (ref "U1") (pin "51") (pinfunction "PTC6_51") (pintype "bidirectional"))
    )
    (net (code "58") (name "PTC7") (class "Default")
      (node (ref "U$4") (pin "5") (pinfunction "MISO/5_5") (pintype "bidirectional"))
      (node (ref "U1") (pin "52") (pinfunction "PTC7_52") (pintype "bidirectional"))
    )
    (net (code "59") (name "PTC8") (class "Default")
      (node (ref "U$4") (pin "6") (pinfunction "IRQ/6_6") (pintype "bidirectional"))
      (node (ref "U1") (pin "53") (pinfunction "PTC8_53") (pintype "bidirectional"))
    )
    (net (code "60") (name "PTC9") (class "Default")
      (node (ref "U$4") (pin "1") (pinfunction "CE/1_1") (pintype "bidirectional"))
      (node (ref "U1") (pin "54") (pinfunction "PTC9_54") (pintype "bidirectional"))
    )
    (net (code "61") (name "PTC10") (class "Default")
      (node (ref "JP1") (pin "12") (pinfunction "12_12") (pintype "passive"))
      (node (ref "U1") (pin "55") (pinfunction "PTC10_55") (pintype "bidirectional"))
    )
    (net (code "62") (name "PTC11") (class "Default")
      (node (ref "JP1") (pin "11") (pinfunction "11_11") (pintype "passive"))
      (node (ref "U1") (pin "56") (pinfunction "PTC11_56") (pintype "bidirectional"))
    )
    (net (code "63") (name "PTD0") (class "Default")
      (node (ref "JP1") (pin "10") (pinfunction "10_10") (pintype "passive"))
      (node (ref "U1") (pin "57") (pinfunction "PTD0_57") (pintype "bidirectional"))
    )
    (net (code "64") (name "PTD1") (class "Default")
      (node (ref "JP1") (pin "9") (pinfunction "9_9") (pintype "passive"))
      (node (ref "U1") (pin "58") (pinfunction "PTD1_58") (pintype "bidirectional"))
    )
    (net (code "65") (name "PTD2") (class "Default")
      (node (ref "JP1") (pin "8") (pinfunction "8_8") (pintype "passive"))
      (node (ref "U1") (pin "59") (pinfunction "PTD2_59") (pintype "bidirectional"))
    )
    (net (code "66") (name "PTD3") (class "Default")
      (node (ref "JP1") (pin "7") (pinfunction "7_7") (pintype "passive"))
      (node (ref "U1") (pin "60") (pinfunction "PTD3_60") (pintype "bidirectional"))
    )
    (net (code "67") (name "PTD4") (class "Default")
      (node (ref "JP1") (pin "6") (pinfunction "6_6") (pintype "passive"))
      (node (ref "U1") (pin "61") (pinfunction "PTD4_61") (pintype "bidirectional"))
    )
    (net (code "68") (name "PTD5") (class "Default")
      (node (ref "JP1") (pin "5") (pinfunction "5_5") (pintype "passive"))
      (node (ref "U1") (pin "62") (pinfunction "PTD5_62") (pintype "bidirectional"))
    )
    (net (code "69") (name "SCL") (class "Default")
      (node (ref "R14") (pin "2") (pinfunction "2_2") (pintype "passive"))
      (node (ref "U1") (pin "37") (pinfunction "PTB2_37") (pintype "bidirectional"))
      (node (ref "U3") (pin "23") (pinfunction "SCLK_23") (pintype "bidirectional"))
    )
    (net (code "70") (name "SDA") (class "Default")
      (node (ref "R13") (pin "2") (pinfunction "2_2") (pintype "passive"))
      (node (ref "U1") (pin "38") (pinfunction "PTB3_38") (pintype "bidirectional"))
      (node (ref "U3") (pin "24") (pinfunction "SDA/MOSI_24") (pintype "bidirectional"))
    )
    (net (code "71") (name "SOFTPOWER") (class "Default")
      (node (ref "R10") (pin "1") (pinfunction "1_1") (pintype "passive"))
      (node (ref "U2") (pin "6") (pinfunction "EN_6") (pintype "input"))
    )
    (net (code "72") (name "SWD_CLK") (class "Default")
      (node (ref "U1") (pin "22") (pinfunction "PTA0_22") (pintype "bidirectional"))
    )
    (net (code "73") (name "SWD_DIO") (class "Default")
      (node (ref "U1") (pin "25") (pinfunction "PTA3_25") (pintype "bidirectional"))
    )
    (net (code "74") (name "USB_D_N") (class "Default")
      (node (ref "U1") (pin "6") (pinfunction "USB0_DM_6") (pintype "bidirectional"))
    )
    (net (code "75") (name "USB_D_P") (class "Default")
      (node (ref "U1") (pin "5") (pinfunction "USB0_DP_5") (pintype "bidirectional"))
    )
    (net (code "76") (name "VCC") (class "Default")
      (node (ref "C1") (pin "1") (pinfunction "1_1") (pintype "passive"))
      (node (ref "C2") (pin "1") (pinfunction "1_1") (pintype "passive"))
      (node (ref "L1") (pin "2") (pinfunction "2_2") (pintype "passive"))
      (node (ref "R10") (pin "2") (pinfunction "2_2") (pintype "passive"))
      (node (ref "R2") (pin "1") (pinfunction "1_1") (pintype "passive"))
      (node (ref "R3") (pin "2") (pinfunction "2_2") (pintype "passive"))
      (node (ref "S1") (pin "1") (pinfunction "O_1") (pintype "passive"))
      (node (ref "U2") (pin "5") (pinfunction "VIN_5") (pintype "power_in"))
    )
    (net (code "77") (name "unconnected-(S1-S-Pad3)") (class "Default")
      (node (ref "S1") (pin "3") (pinfunction "S_3") (pintype "passive"))
    )
    (net (code "78") (name "unconnected-(U$6-PadDVDD{slash}24)") (class "Default")
      (node (ref "U$6") (pin "DVDD/24") (pinfunction "DVDD/24_DVDD/24") (pintype "bidirectional"))
    )
    (net (code "79") (name "unconnected-(U$6-PadMTDI{slash}10)") (class "Default")
      (node (ref "U$6") (pin "MTDI/10") (pinfunction "MTDI/10_MTDI/10") (pintype "bidirectional"))
    )
    (net (code "80") (name "unconnected-(U$6-PadMTDO{slash}13)") (class "Default")
      (node (ref "U$6") (pin "MTDO/13") (pinfunction "MTDO/13_MTDO/13") (pintype "bidirectional"))
    )
    (net (code "81") (name "unconnected-(U$6-PadMTMS{slash}9)") (class "Default")
      (node (ref "U$6") (pin "MTMS/9") (pinfunction "MTMS/9_MTMS/9") (pintype "bidirectional"))
    )
    (net (code "82") (name "unconnected-(U$6-PadTOUT{slash}6)") (class "Default")
      (node (ref "U$6") (pin "TOUT/6") (pinfunction "TOUT/6_TOUT/6") (pintype "bidirectional"))
    )
    (net (code "83") (name "unconnected-(U$6-PadU0RXD{slash}25)") (class "Default")
      (node (ref "U$6") (pin "U0RXD/25") (pinfunction "U0RXD/25_U0RXD/25") (pintype "bidirectional"))
    )
    (net (code "84") (name "unconnected-(U$6-PadVDDA{slash}30)") (class "Default")
      (node (ref "U$6") (pin "VDDA/30") (pinfunction "VDDA/30_VDDA/30") (pintype "bidirectional"))
    )
    (net (code "85") (name "unconnected-(U$6-PadVDD_RTC{slash}5)") (class "Default")
      (node (ref "U$6") (pin "VDD_RTC/5") (pinfunction "VDD_RTC/5_VDD_RTC/5") (pintype "bidirectional"))
    )
    (net (code "86") (name "unconnected-(U$6-PadVDD{slash}16)") (class "Default")
      (node (ref "U$6") (pin "VDD/16") (pinfunction "VDD/16_VDD/16") (pintype "bidirectional"))
    )
    (net (code "87") (name "unconnected-(U$6-PadXPD_DCDC{slash}8)") (class "Default")
      (node (ref "U$6") (pin "XPD_DCDC/8") (pinfunction "XPD_DCDC/8_XPD_DCDC/8") (pintype "bidirectional"))
    )
    (net (code "88") (name "unconnected-(U1-ADC0_DM0-Pad10)") (class "Default")
      (node (ref "U1") (pin "10") (pinfunction "ADC0_DM0_10") (pintype "bidirectional"))
    )
    (net (code "89") (name "unconnected-(U1-ADC0_DM3-Pad12)") (class "Default")
      (node (ref "U1") (pin "12") (pinfunction "ADC0_DM3_12") (pintype "bidirectional"))
    )
    (net (code "90") (name "unconnected-(U1-ADC0_DP0-Pad9)") (class "Default")
      (node (ref "U1") (pin "9") (pinfunction "ADC0_DP0_9") (pintype "bidirectional"))
    )
    (net (code "91") (name "unconnected-(U1-ADC0_DP3-Pad11)") (class "Default")
      (node (ref "U1") (pin "11") (pinfunction "ADC0_DP3_11") (pintype "bidirectional"))
    )
    (net (code "92") (name "unconnected-(U1-DAC0-Pad18)") (class "Default")
      (node (ref "U1") (pin "18") (pinfunction "DAC0_18") (pintype "bidirectional"))
    )
    (net (code "93") (name "unconnected-(U1-PTA1-Pad23)") (class "Default")
      (node (ref "U1") (pin "23") (pinfunction "PTA1_23") (pintype "bidirectional"))
    )
    (net (code "94") (name "unconnected-(U1-PTA2-Pad24)") (class "Default")
      (node (ref "U1") (pin "24") (pinfunction "PTA2_24") (pintype "bidirectional"))
    )
    (net (code "95") (name "unconnected-(U1-PTA4-Pad26)") (class "Default")
      (node (ref "U1") (pin "26") (pinfunction "PTA4_26") (pintype "bidirectional"))
    )
    (net (code "96") (name "unconnected-(U1-PTA5-Pad27)") (class "Default")
      (node (ref "U1") (pin "27") (pinfunction "PTA5_27") (pintype "bidirectional"))
    )
    (net (code "97") (name "unconnected-(U1-PTA12-Pad28)") (class "Default")
      (node (ref "U1") (pin "28") (pinfunction "PTA12_28") (pintype "bidirectional"))
    )
    (net (code "98") (name "unconnected-(U1-PTA13-Pad29)") (class "Default")
      (node (ref "U1") (pin "29") (pinfunction "PTA13_29") (pintype "bidirectional"))
    )
    (net (code "99") (name "unconnected-(U1-PTD7-Pad64)") (class "Default")
      (node (ref "U1") (pin "64") (pinfunction "PTD7_64") (pintype "bidirectional"))
    )
    (net (code "100") (name "unconnected-(U1-PTE0-Pad1)") (class "Default")
      (node (ref "U1") (pin "1") (pinfunction "PTE0_1") (pintype "bidirectional"))
    )
    (net (code "101") (name "unconnected-(U1-PTE1-Pad2)") (class "Default")
      (node (ref "U1") (pin "2") (pinfunction "PTE1_2") (pintype "bidirectional"))
    )
    (net (code "102") (name "unconnected-(U1-RESET_B-Pad34)") (class "Default")
      (node (ref "U1") (pin "34") (pinfunction "RESET_B_34") (pintype "bidirectional"))
    )
    (net (code "103") (name "unconnected-(U3-AUX_CL-Pad7)") (class "Default")
      (node (ref "U3") (pin "7") (pinfunction "AUX_CL_7") (pintype "bidirectional"))
    )
    (net (code "104") (name "unconnected-(U3-AUX_DA-Pad21)") (class "Default")
      (node (ref "U3") (pin "21") (pinfunction "AUX_DA_21") (pintype "bidirectional"))
    )
  )
)
